# MegaSheild2.net
KiCad netlist of a schematic drawn in EAGLE
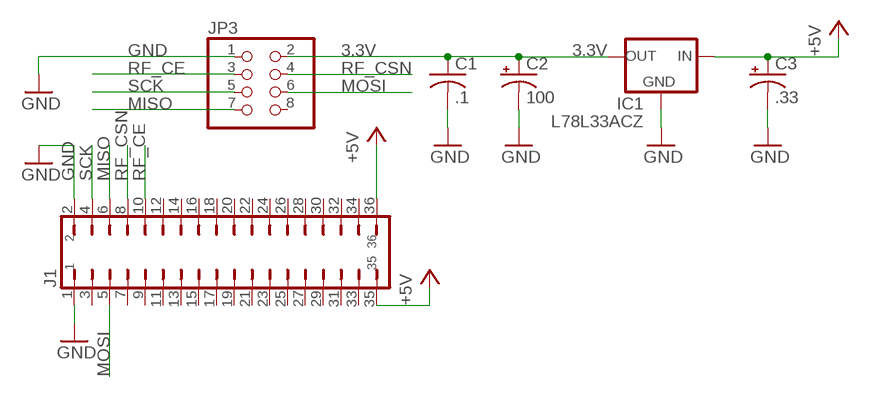
[diagram p0: schematic, sheet 1]

(export (version "E")
  (design (tool "Eeschema 10.0.6"))
  (components
    (comp (ref "C1")
      (value ".1")
      (footprint "eagle-import:C025-024X044")
      (libsource (lib "eagle-import") (part "C-US025-024X044"))
    )
    (comp (ref "C2")
      (value "100")
      (footprint "eagle-import:E2,5-6")
      (libsource (lib "eagle-import") (part "CPOL-USE2.5-6"))
    )
    (comp (ref "C3")
      (value ".33")
      (footprint "eagle-import:E1,8-4")
      (libsource (lib "eagle-import") (part "CPOL-USE1.8-4"))
    )
    (comp (ref "IC1")
      (value "L78L33ACZ")
      (footprint "eagle-import:78LXX")
      (libsource (lib "eagle-import") (part "78LXX"))
    )
    (comp (ref "J1")
      (value "JP18Q2X18BIG")
      (footprint "eagle-import:2X18-BIG")
      (libsource (lib "eagle-import") (part "JP18Q2X18BIG"))
    )
    (comp (ref "JP3")
      (value "PINHD-2X4")
      (footprint "eagle-import:2X04")
      (libsource (lib "eagle-import") (part "PINHD-2X4"))
    )
  )
  (nets
    (net (code "1") (name "+5V") (class "Default")
      (node (ref "C3") (pin "+") (pinfunction "+_+") (pintype "passive"))
      (node (ref "IC1") (pin "IN") (pinfunction "IN_IN") (pintype "input"))
      (node (ref "J1") (pin "35") (pinfunction "35_35") (pintype "passive"))
      (node (ref "J1") (pin "36") (pinfunction "36_36") (pintype "passive"))
    )
    (net (code "2") (name "/3.3V") (class "Default")
      (node (ref "C1") (pin "1") (pinfunction "1_1") (pintype "passive"))
      (node (ref "C2") (pin "+") (pinfunction "+_+") (pintype "passive"))
      (node (ref "IC1") (pin "OUT") (pinfunction "OUT_OUT") (pintype "passive"))
      (node (ref "JP3") (pin "2") (pinfunction "2_2") (pintype "passive"))
    )
    (net (code "3") (name "/MISO") (class "Default")
      (node (ref "J1") (pin "6") (pinfunction "6_6") (pintype "passive"))
      (node (ref "JP3") (pin "7") (pinfunction "7_7") (pintype "passive"))
    )
    (net (code "4") (name "/MOSI") (class "Default")
      (node (ref "J1") (pin "5") (pinfunction "5_5") (pintype "passive"))
      (node (ref "JP3") (pin "6") (pinfunction "6_6") (pintype "passive"))
    )
    (net (code "5") (name "/RF_CE") (class "Default")
      (node (ref "J1") (pin "10") (pinfunction "10_10") (pintype "passive"))
      (node (ref "JP3") (pin "3") (pinfunction "3_3") (pintype "passive"))
    )
    (net (code "6") (name "/RF_CSN") (class "Default")
      (node (ref "J1") (pin "8") (pinfunction "8_8") (pintype "passive"))
      (node (ref "JP3") (pin "4") (pinfunction "4_4") (pintype "passive"))
    )
    (net (code "7") (name "/SCK") (class "Default")
      (node (ref "J1") (pin "4") (pinfunction "4_4") (pintype "passive"))
      (node (ref "JP3") (pin "5") (pinfunction "5_5") (pintype "passive"))
    )
    (net (code "8") (name "GND") (class "Default")
      (node (ref "C1") (pin "2") (pinfunction "2_2") (pintype "passive"))
      (node (ref "C2") (pin "-") (pinfunction "-_-") (pintype "passive"))
      (node (ref "C3") (pin "-") (pinfunction "-_-") (pintype "passive"))
      (node (ref "IC1") (pin "GND") (pinfunction "GND_GND") (pintype "input"))
      (node (ref "J1") (pin "1") (pinfunction "1_1") (pintype "passive"))
      (node (ref "J1") (pin "2") (pinfunction "2_2") (pintype "passive"))
      (node (ref "JP3") (pin "1") (pinfunction "1_1") (pintype "passive"))
    )
    (net (code "9") (name "unconnected-(J1-Pad3)") (class "Default")
      (node (ref "J1") (pin "3") (pinfunction "3_3") (pintype "passive"))
    )
    (net (code "10") (name "unconnected-(J1-Pad7)") (class "Default")
      (node (ref "J1") (pin "7") (pinfunction "7_7") (pintype "passive"))
    )
    (net (code "11") (name "unconnected-(J1-Pad9)") (class "Default")
      (node (ref "J1") (pin "9") (pinfunction "9_9") (pintype "passive"))
    )
    (net (code "12") (name "unconnected-(J1-Pad11)") (class "Default")
      (node (ref "J1") (pin "11") (pinfunction "11_11") (pintype "passive"))
    )
    (net (code "13") (name "unconnected-(J1-Pad12)") (class "Default")
      (node (ref "J1") (pin "12") (pinfunction "12_12") (pintype "passive"))
    )
    (net (code "14") (name "unconnected-(J1-Pad13)") (class "Default")
      (node (ref "J1") (pin "13") (pinfunction "13_13") (pintype "passive"))
    )
    (net (code "15") (name "unconnected-(J1-Pad14)") (class "Default")
      (node (ref "J1") (pin "14") (pinfunction "14_14") (pintype "passive"))
    )
    (net (code "16") (name "unconnected-(J1-Pad15)") (class "Default")
      (node (ref "J1") (pin "15") (pinfunction "15_15") (pintype "passive"))
    )
    (net (code "17") (name "unconnected-(J1-Pad16)") (class "Default")
      (node (ref "J1") (pin "16") (pinfunction "16_16") (pintype "passive"))
    )
    (net (code "18") (name "unconnected-(J1-Pad17)") (class "Default")
      (node (ref "J1") (pin "17") (pinfunction "17_17") (pintype "passive"))
    )
    (net (code "19") (name "unconnected-(J1-Pad18)") (class "Default")
      (node (ref "J1") (pin "18") (pinfunction "18_18") (pintype "passive"))
    )
    (net (code "20") (name "unconnected-(J1-Pad19)") (class "Default")
      (node (ref "J1") (pin "19") (pinfunction "19_19") (pintype "passive"))
    )
    (net (code "21") (name "unconnected-(J1-Pad20)") (class "Default")
      (node (ref "J1") (pin "20") (pinfunction "20_20") (pintype "passive"))
    )
    (net (code "22") (name "unconnected-(J1-Pad21)") (class "Default")
      (node (ref "J1") (pin "21") (pinfunction "21_21") (pintype "passive"))
    )
    (net (code "23") (name "unconnected-(J1-Pad22)") (class "Default")
      (node (ref "J1") (pin "22") (pinfunction "22_22") (pintype "passive"))
    )
    (net (code "24") (name "unconnected-(J1-Pad23)") (class "Default")
      (node (ref "J1") (pin "23") (pinfunction "23_23") (pintype "passive"))
    )
    (net (code "25") (name "unconnected-(J1-Pad24)") (class "Default")
      (node (ref "J1") (pin "24") (pinfunction "24_24") (pintype "passive"))
    )
    (net (code "26") (name "unconnected-(J1-Pad25)") (class "Default")
      (node (ref "J1") (pin "25") (pinfunction "25_25") (pintype "passive"))
    )
    (net (code "27") (name "unconnected-(J1-Pad26)") (class "Default")
      (node (ref "J1") (pin "26") (pinfunction "26_26") (pintype "passive"))
    )
    (net (code "28") (name "unconnected-(J1-Pad27)") (class "Default")
      (node (ref "J1") (pin "27") (pinfunction "27_27") (pintype "passive"))
    )
    (net (code "29") (name "unconnected-(J1-Pad28)") (class "Default")
      (node (ref "J1") (pin "28") (pinfunction "28_28") (pintype "passive"))
    )
    (net (code "30") (name "unconnected-(J1-Pad29)") (class "Default")
      (node (ref "J1") (pin "29") (pinfunction "29_29") (pintype "passive"))
    )
    (net (code "31") (name "unconnected-(J1-Pad30)") (class "Default")
      (node (ref "J1") (pin "30") (pinfunction "30_30") (pintype "passive"))
    )
    (net (code "32") (name "unconnected-(J1-Pad31)") (class "Default")
      (node (ref "J1") (pin "31") (pinfunction "31_31") (pintype "passive"))
    )
    (net (code "33") (name "unconnected-(J1-Pad32)") (class "Default")
      (node (ref "J1") (pin "32") (pinfunction "32_32") (pintype "passive"))
    )
    (net (code "34") (name "unconnected-(J1-Pad33)") (class "Default")
      (node (ref "J1") (pin "33") (pinfunction "33_33") (pintype "passive"))
    )
    (net (code "35") (name "unconnected-(J1-Pad34)") (class "Default")
      (node (ref "J1") (pin "34") (pinfunction "34_34") (pintype "passive"))
    )
    (net (code "36") (name "unconnected-(JP3-Pad8)") (class "Default")
      (node (ref "JP3") (pin "8") (pinfunction "8_8") (pintype "passive"))
    )
  )
)
